# uSD.net
KiCad netlist of a schematic drawn in Altium Designer
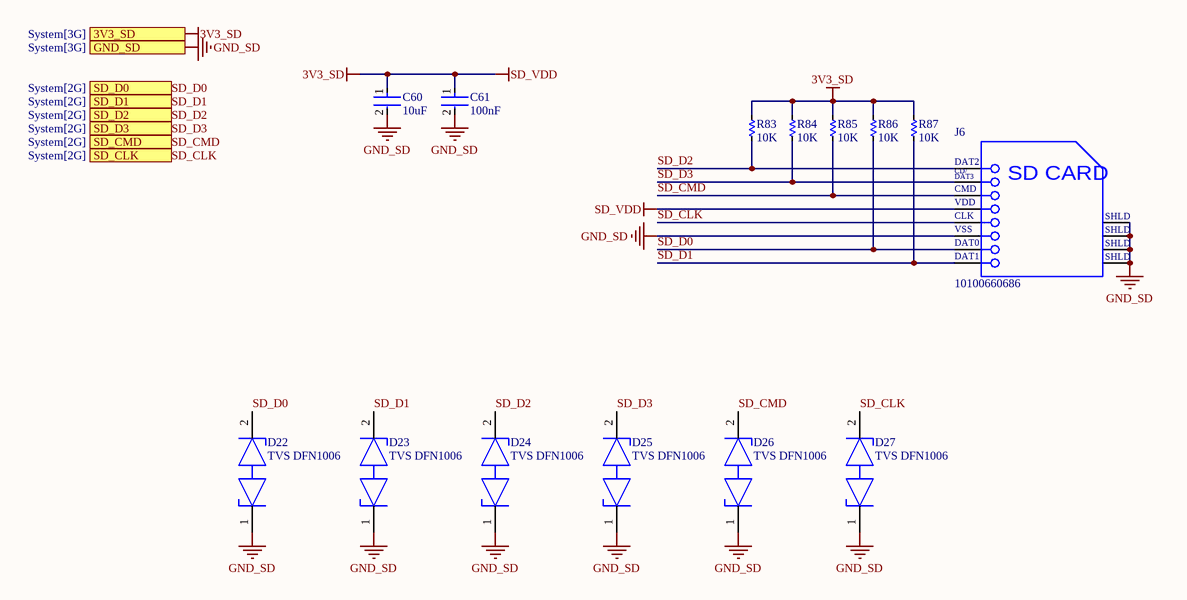
[diagram p0: uSD.SchDoc]

(export (version "E")
  (design (tool "Eeschema 10.0.6"))
  (components
    (comp (ref "C60")
      (value "10uF")
      (footprint "FP-GRM18-0_15-MFG")
      (description "CAP CER 10V X5R 0603")
      (fields
        (field (name "OCTOPART") "https://octopart.com/grm188r61a106ke69d-murata-22851381")
        (field (name "MANUFACTURER PART NUMBER") "GRM188R61A106KE69D")
      )
      (libsource (lib "Altium Content Vault") (part "11868f565c42a9108669ba33697ecf6"))
    )
    (comp (ref "C61")
      (value "100nF")
      (footprint "FP-GRM18-0_15-MFG")
      (description "CAP CER 10V X5R 0603")
      (fields
        (field (name "OCTOPART") "https://octopart.com/grm188r61a106ke69d-murata-22851381")
        (field (name "MANUFACTURER PART NUMBER") "GRM188R61A106KE69D")
      )
      (libsource (lib "Altium Content Vault") (part "11868f565c42a9108669ba33697ecf6"))
    )
    (comp (ref "D22")
      (value "TVS DFN1006")
      (footprint "FP-SOD882-CA-MFG")
      (description "PESDNC2FD3V3B TVS DIODE DFN1006")
      (libsource (lib "Altium Content Vault") (part "f99c6b8f7582c6664fd8d1097682dbe"))
    )
    (comp (ref "D23")
      (value "TVS DFN1006")
      (footprint "FP-SOD882-CA-MFG")
      (description "PESDNC2FD3V3B TVS DIODE DFN1006")
      (libsource (lib "Altium Content Vault") (part "f99c6b8f7582c6664fd8d1097682dbe"))
    )
    (comp (ref "D24")
      (value "TVS DFN1006")
      (footprint "FP-SOD882-CA-MFG")
      (description "PESDNC2FD3V3B TVS DIODE DFN1006")
      (libsource (lib "Altium Content Vault") (part "f99c6b8f7582c6664fd8d1097682dbe"))
    )
    (comp (ref "D25")
      (value "TVS DFN1006")
      (footprint "FP-SOD882-CA-MFG")
      (description "PESDNC2FD3V3B TVS DIODE DFN1006")
      (libsource (lib "Altium Content Vault") (part "f99c6b8f7582c6664fd8d1097682dbe"))
    )
    (comp (ref "D26")
      (value "TVS DFN1006")
      (footprint "FP-SOD882-CA-MFG")
      (description "PESDNC2FD3V3B TVS DIODE DFN1006")
      (libsource (lib "Altium Content Vault") (part "f99c6b8f7582c6664fd8d1097682dbe"))
    )
    (comp (ref "D27")
      (value "TVS DFN1006")
      (footprint "FP-SOD882-CA-MFG")
      (description "PESDNC2FD3V3B TVS DIODE DFN1006")
      (libsource (lib "Altium Content Vault") (part "f99c6b8f7582c6664fd8d1097682dbe"))
    )
    (comp (ref "J6")
      (value "10100660686")
      (footprint "AMPH-10100660686_V")
      (description "Micro SD Card Reader, -25 to 85 degC, 9-Pin SMD, RoHS, Tape and Reel")
      (fields (field (name "MANUFACTURER") "Amphenol") (field (name "PARTNUMBER") "10100660"))
      (libsource (lib "Altium Content Vault") (part "CN-SD-8-4S"))
    )
    (comp (ref "R83")
      (value "10K")
      (footprint "RES-SMD-0603")
      (description "Res 0603 5%")
      (fields
        (field (name "MANUFACTURER") "Generic Components")
        (field (name "PUBLISHER") "Altium Hobart Technology Centre")
      )
      (libsource (lib "TechMT.VN_Lib_Project v2") (part "Res-SMD"))
    )
    (comp (ref "R84")
      (value "10K")
      (footprint "RES-SMD-0603")
      (description "Res 0603 5%")
      (fields
        (field (name "MANUFACTURER") "Generic Components")
        (field (name "PUBLISHER") "Altium Hobart Technology Centre")
      )
      (libsource (lib "TechMT.VN_Lib_Project v2") (part "Res-SMD"))
    )
    (comp (ref "R85")
      (value "10K")
      (footprint "RES-SMD-0603")
      (description "Res 0603 5%")
      (fields
        (field (name "MANUFACTURER") "Generic Components")
        (field (name "PUBLISHER") "Altium Hobart Technology Centre")
      )
      (libsource (lib "TechMT.VN_Lib_Project v2") (part "Res-SMD"))
    )
    (comp (ref "R86")
      (value "10K")
      (footprint "RES-SMD-0603")
      (description "Res 0603 5%")
      (fields
        (field (name "MANUFACTURER") "Generic Components")
        (field (name "PUBLISHER") "Altium Hobart Technology Centre")
      )
      (libsource (lib "TechMT.VN_Lib_Project v2") (part "Res-SMD"))
    )
    (comp (ref "R87")
      (value "10K")
      (footprint "RES-SMD-0603")
      (description "Res 0603 5%")
      (fields
        (field (name "MANUFACTURER") "Generic Components")
        (field (name "PUBLISHER") "Altium Hobart Technology Centre")
      )
      (libsource (lib "TechMT.VN_Lib_Project v2") (part "Res-SMD"))
    )
  )
  (nets
    (net (code "1") (name "/SD_CLK") (class "Default")
      (node (ref "D27") (pin "2") (pinfunction "K2_2") (pintype "passive"))
      (node (ref "J6") (pin "5") (pinfunction "CLK_5") (pintype "passive"))
    )
    (net (code "2") (name "/SD_CMD") (class "Default")
      (node (ref "D26") (pin "2") (pinfunction "K2_2") (pintype "passive"))
      (node (ref "J6") (pin "3") (pinfunction "CMD_3") (pintype "passive"))
      (node (ref "R85") (pin "1") (pinfunction "1_1") (pintype "passive"))
    )
    (net (code "3") (name "/SD_D0") (class "Default")
      (node (ref "D22") (pin "2") (pinfunction "K2_2") (pintype "passive"))
      (node (ref "J6") (pin "7") (pinfunction "DAT0_7") (pintype "passive"))
      (node (ref "R86") (pin "1") (pinfunction "1_1") (pintype "passive"))
    )
    (net (code "4") (name "/SD_D1") (class "Default")
      (node (ref "D23") (pin "2") (pinfunction "K2_2") (pintype "passive"))
      (node (ref "J6") (pin "8") (pinfunction "DAT1_8") (pintype "passive"))
      (node (ref "R87") (pin "1") (pinfunction "1_1") (pintype "passive"))
    )
    (net (code "5") (name "/SD_D2") (class "Default")
      (node (ref "D24") (pin "2") (pinfunction "K2_2") (pintype "passive"))
      (node (ref "J6") (pin "1") (pinfunction "DAT2_1") (pintype "passive"))
      (node (ref "R83") (pin "1") (pinfunction "1_1") (pintype "passive"))
    )
    (net (code "6") (name "/SD_D3") (class "Default")
      (node (ref "D25") (pin "2") (pinfunction "K2_2") (pintype "passive"))
      (node (ref "J6") (pin "2") (pinfunction "CD/DAT3_2") (pintype "passive"))
      (node (ref "R84") (pin "1") (pinfunction "1_1") (pintype "passive"))
    )
    (net (code "7") (name "3V3_SD") (class "Default")
      (node (ref "C60") (pin "1") (pinfunction "1_1") (pintype "passive"))
      (node (ref "C61") (pin "1") (pinfunction "1_1") (pintype "passive"))
      (node (ref "J6") (pin "4") (pinfunction "VDD_4") (pintype "passive"))
      (node (ref "R83") (pin "2") (pinfunction "2_2") (pintype "passive"))
      (node (ref "R84") (pin "2") (pinfunction "2_2") (pintype "passive"))
      (node (ref "R85") (pin "2") (pinfunction "2_2") (pintype "passive"))
      (node (ref "R86") (pin "2") (pinfunction "2_2") (pintype "passive"))
      (node (ref "R87") (pin "2") (pinfunction "2_2") (pintype "passive"))
    )
    (net (code "8") (name "GND_SD") (class "Default")
      (node (ref "C60") (pin "2") (pinfunction "2_2") (pintype "passive"))
      (node (ref "C61") (pin "2") (pinfunction "2_2") (pintype "passive"))
      (node (ref "D22") (pin "1") (pinfunction "K1_1") (pintype "passive"))
      (node (ref "D23") (pin "1") (pinfunction "K1_1") (pintype "passive"))
      (node (ref "D24") (pin "1") (pinfunction "K1_1") (pintype "passive"))
      (node (ref "D25") (pin "1") (pinfunction "K1_1") (pintype "passive"))
      (node (ref "D26") (pin "1") (pinfunction "K1_1") (pintype "passive"))
      (node (ref "D27") (pin "1") (pinfunction "K1_1") (pintype "passive"))
      (node (ref "J6") (pin "10") (pinfunction "SHLD_10") (pintype "passive"))
      (node (ref "J6") (pin "11") (pinfunction "SHLD_11") (pintype "passive"))
      (node (ref "J6") (pin "12") (pinfunction "SHLD_12") (pintype "passive"))
      (node (ref "J6") (pin "6") (pinfunction "VSS_6") (pintype "passive"))
      (node (ref "J6") (pin "9") (pinfunction "SHLD_9") (pintype "passive"))
    )
  )
)
